# CascaMesa.net
KiCad netlist of a schematic drawn in EAGLE
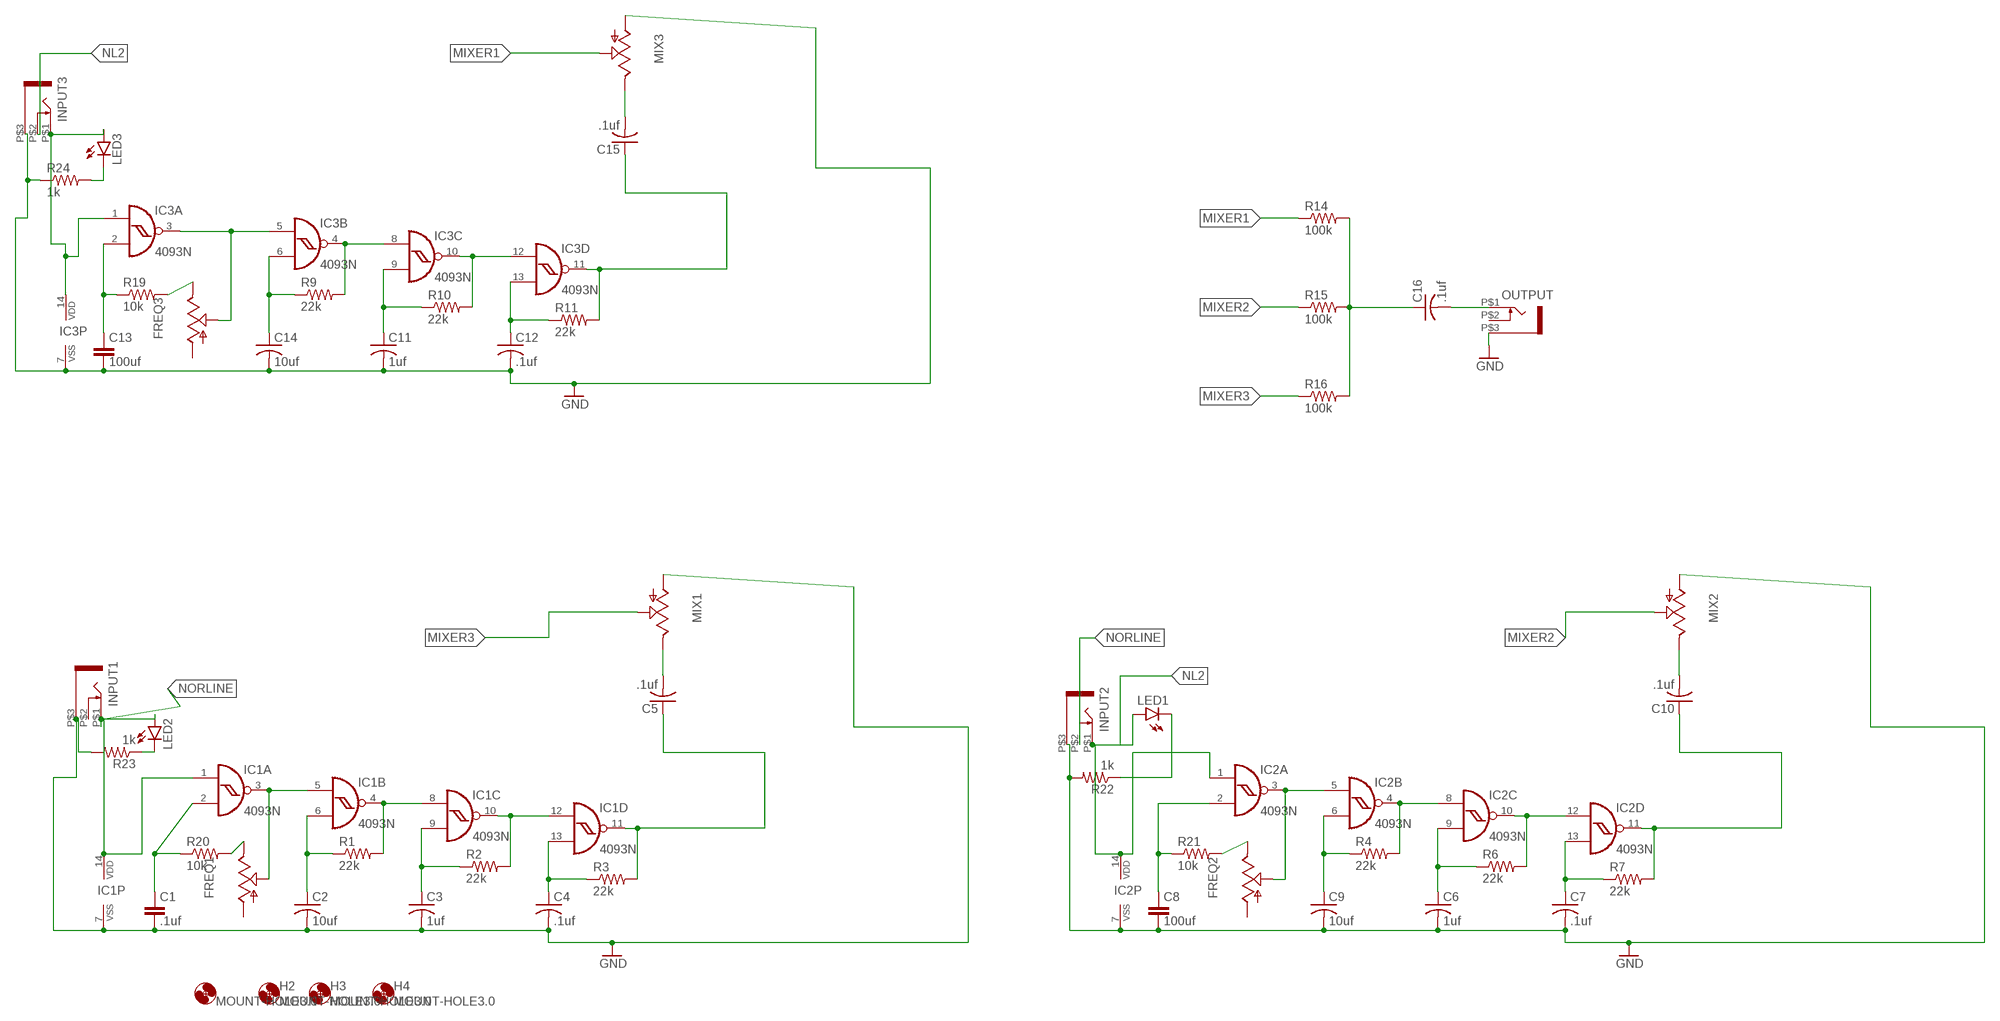
[diagram p0: schematic, sheet 1]

(export (version "E")
  (design (tool "Eeschema 10.0.6"))
  (components
    (comp (ref "C1")
      (value ".1uf")
      (footprint "eagle-import:C050-025X075")
      (libsource (lib "eagle-import") (part "C-EU050-025X075"))
    )
    (comp (ref "C2")
      (value "10uf")
      (footprint "eagle-import:C050-025X075")
      (libsource (lib "eagle-import") (part "C-US050-025X075"))
    )
    (comp (ref "C3")
      (value "1uf")
      (footprint "eagle-import:C050-025X075")
      (libsource (lib "eagle-import") (part "C-US050-025X075"))
    )
    (comp (ref "C4")
      (value ".1uf")
      (footprint "eagle-import:C050-025X075")
      (libsource (lib "eagle-import") (part "C-US050-025X075"))
    )
    (comp (ref "C5")
      (value ".1uf")
      (footprint "eagle-import:C050-025X075")
      (libsource (lib "eagle-import") (part "C-US050-025X075"))
    )
    (comp (ref "C6")
      (value "1uf")
      (footprint "eagle-import:C050-025X075")
      (libsource (lib "eagle-import") (part "C-US050-025X075"))
    )
    (comp (ref "C7")
      (value ".1uf")
      (footprint "eagle-import:C050-025X075")
      (libsource (lib "eagle-import") (part "C-US050-025X075"))
    )
    (comp (ref "C8")
      (value "100uf")
      (footprint "eagle-import:C050-025X075")
      (libsource (lib "eagle-import") (part "C-EU050-025X075"))
    )
    (comp (ref "C9")
      (value "10uf")
      (footprint "eagle-import:C050-025X075")
      (libsource (lib "eagle-import") (part "C-US050-025X075"))
    )
    (comp (ref "C10")
      (value ".1uf")
      (footprint "eagle-import:C050-025X075")
      (libsource (lib "eagle-import") (part "C-US050-025X075"))
    )
    (comp (ref "C11")
      (value "1uf")
      (footprint "eagle-import:C050-025X075")
      (libsource (lib "eagle-import") (part "C-US050-025X075"))
    )
    (comp (ref "C12")
      (value ".1uf")
      (footprint "eagle-import:C050-025X075")
      (libsource (lib "eagle-import") (part "C-US050-025X075"))
    )
    (comp (ref "C13")
      (value "100uf")
      (footprint "eagle-import:C050-025X075")
      (libsource (lib "eagle-import") (part "C-EU050-025X075"))
    )
    (comp (ref "C14")
      (value "10uf")
      (footprint "eagle-import:C050-025X075")
      (libsource (lib "eagle-import") (part "C-US050-025X075"))
    )
    (comp (ref "C15")
      (value ".1uf")
      (footprint "eagle-import:C050-025X075")
      (libsource (lib "eagle-import") (part "C-US050-025X075"))
    )
    (comp (ref "C16")
      (value ".1uf")
      (footprint "eagle-import:C050-025X075")
      (libsource (lib "eagle-import") (part "C-US050-025X075"))
    )
    (comp (ref "FREQ1")
      (value "9MM_SNAP-IN_POT_")
      (footprint "eagle-import:9MM_SNAP-IN_POT")
      (libsource (lib "eagle-import") (part "9MM_SNAP-IN_POT_"))
    )
    (comp (ref "FREQ2")
      (value "9MM_SNAP-IN_POT_")
      (footprint "eagle-import:9MM_SNAP-IN_POT")
      (libsource (lib "eagle-import") (part "9MM_SNAP-IN_POT_"))
    )
    (comp (ref "FREQ3")
      (value "9MM_SNAP-IN_POT_")
      (footprint "eagle-import:9MM_SNAP-IN_POT")
      (libsource (lib "eagle-import") (part "9MM_SNAP-IN_POT_"))
    )
    (comp (ref "H1")
      (value "MOUNT-HOLE3.0")
      (footprint "eagle-import:3,0")
      (libsource (lib "eagle-import") (part "MOUNT-HOLE3.0"))
    )
    (comp (ref "H2")
      (value "MOUNT-HOLE3.0")
      (footprint "eagle-import:3,0")
      (libsource (lib "eagle-import") (part "MOUNT-HOLE3.0"))
    )
    (comp (ref "H3")
      (value "MOUNT-HOLE3.0")
      (footprint "eagle-import:3,0")
      (libsource (lib "eagle-import") (part "MOUNT-HOLE3.0"))
    )
    (comp (ref "H4")
      (value "MOUNT-HOLE3.0")
      (footprint "eagle-import:3,0")
      (libsource (lib "eagle-import") (part "MOUNT-HOLE3.0"))
    )
    (comp (ref "IC1")
      (value "4093N")
      (footprint "eagle-import:DIL14")
      (libsource (lib "eagle-import") (part "4093N"))
    )
    (comp (ref "IC2")
      (value "4093N")
      (footprint "eagle-import:DIL14")
      (libsource (lib "eagle-import") (part "4093N"))
    )
    (comp (ref "IC3")
      (value "4093N")
      (footprint "eagle-import:DIL14")
      (libsource (lib "eagle-import") (part "4093N"))
    )
    (comp (ref "INPUT1")
      (value "WQP-PJ301M-12_JACK")
      (footprint "eagle-import:WQP-PJ301M-12_JACK")
      (libsource (lib "eagle-import") (part "WQP-PJ301M-12_JACK"))
    )
    (comp (ref "INPUT2")
      (value "WQP-PJ301M-12_JACK")
      (footprint "eagle-import:WQP-PJ301M-12_JACK")
      (libsource (lib "eagle-import") (part "WQP-PJ301M-12_JACK"))
    )
    (comp (ref "INPUT3")
      (value "WQP-PJ301M-12_JACK")
      (footprint "eagle-import:WQP-PJ301M-12_JACK")
      (libsource (lib "eagle-import") (part "WQP-PJ301M-12_JACK"))
    )
    (comp (ref "LED1")
      (value "LED3MM")
      (footprint "eagle-import:LED3MM")
      (libsource (lib "eagle-import") (part "LED3MM"))
    )
    (comp (ref "LED2")
      (value "LED3MM")
      (footprint "eagle-import:LED3MM")
      (libsource (lib "eagle-import") (part "LED3MM"))
    )
    (comp (ref "LED3")
      (value "LED3MM")
      (footprint "eagle-import:LED3MM")
      (libsource (lib "eagle-import") (part "LED3MM"))
    )
    (comp (ref "MIX1")
      (value "9MM_SNAP-IN_POT_")
      (footprint "eagle-import:9MM_SNAP-IN_POT")
      (libsource (lib "eagle-import") (part "9MM_SNAP-IN_POT_"))
    )
    (comp (ref "MIX2")
      (value "9MM_SNAP-IN_POT_")
      (footprint "eagle-import:9MM_SNAP-IN_POT")
      (libsource (lib "eagle-import") (part "9MM_SNAP-IN_POT_"))
    )
    (comp (ref "MIX3")
      (value "9MM_SNAP-IN_POT_")
      (footprint "eagle-import:9MM_SNAP-IN_POT")
      (libsource (lib "eagle-import") (part "9MM_SNAP-IN_POT_"))
    )
    (comp (ref "OUTPUT")
      (value "WQP-PJ301M-12_JACK")
      (footprint "eagle-import:WQP-PJ301M-12_JACK")
      (libsource (lib "eagle-import") (part "WQP-PJ301M-12_JACK"))
    )
    (comp (ref "R1")
      (value "22k")
      (footprint "eagle-import:0207_7")
      (libsource (lib "eagle-import") (part "R-US_0207/7"))
    )
    (comp (ref "R2")
      (value "22k")
      (footprint "eagle-import:0207_7")
      (libsource (lib "eagle-import") (part "R-US_0207/7"))
    )
    (comp (ref "R3")
      (value "22k")
      (footprint "eagle-import:0207_7")
      (libsource (lib "eagle-import") (part "R-US_0207/7"))
    )
    (comp (ref "R4")
      (value "22k")
      (footprint "eagle-import:0207_7")
      (libsource (lib "eagle-import") (part "R-US_0207/7"))
    )
    (comp (ref "R6")
      (value "22k")
      (footprint "eagle-import:0207_7")
      (libsource (lib "eagle-import") (part "R-US_0207/7"))
    )
    (comp (ref "R7")
      (value "22k")
      (footprint "eagle-import:0207_7")
      (libsource (lib "eagle-import") (part "R-US_0207/7"))
    )
    (comp (ref "R9")
      (value "22k")
      (footprint "eagle-import:0207_7")
      (libsource (lib "eagle-import") (part "R-US_0207/7"))
    )
    (comp (ref "R10")
      (value "22k")
      (footprint "eagle-import:0207_7")
      (libsource (lib "eagle-import") (part "R-US_0207/7"))
    )
    (comp (ref "R11")
      (value "22k")
      (footprint "eagle-import:0207_7")
      (libsource (lib "eagle-import") (part "R-US_0207/7"))
    )
    (comp (ref "R14")
      (value "100k")
      (footprint "eagle-import:0207_7")
      (libsource (lib "eagle-import") (part "R-US_0207/7"))
    )
    (comp (ref "R15")
      (value "100k")
      (footprint "eagle-import:0207_7")
      (libsource (lib "eagle-import") (part "R-US_0207/7"))
    )
    (comp (ref "R16")
      (value "100k")
      (footprint "eagle-import:0207_7")
      (libsource (lib "eagle-import") (part "R-US_0207/7"))
    )
    (comp (ref "R19")
      (value "10k")
      (footprint "eagle-import:0207_7")
      (libsource (lib "eagle-import") (part "R-US_0207/7"))
    )
    (comp (ref "R20")
      (value "10k")
      (footprint "eagle-import:0207_7")
      (libsource (lib "eagle-import") (part "R-US_0207/7"))
    )
    (comp (ref "R21")
      (value "10k")
      (footprint "eagle-import:0207_7")
      (libsource (lib "eagle-import") (part "R-US_0207/7"))
    )
    (comp (ref "R22")
      (value "1k")
      (footprint "eagle-import:0207_7")
      (libsource (lib "eagle-import") (part "R-US_0207/7"))
    )
    (comp (ref "R23")
      (value "1k")
      (footprint "eagle-import:0207_7")
      (libsource (lib "eagle-import") (part "R-US_0207/7"))
    )
    (comp (ref "R24")
      (value "1k")
      (footprint "eagle-import:0207_7")
      (libsource (lib "eagle-import") (part "R-US_0207/7"))
    )
  )
  (nets
    (net (code "1") (name "GND") (class "Default")
      (node (ref "C1") (pin "2") (pinfunction "2_2") (pintype "passive"))
      (node (ref "C11") (pin "2") (pinfunction "2_2") (pintype "passive"))
      (node (ref "C12") (pin "2") (pinfunction "2_2") (pintype "passive"))
      (node (ref "C13") (pin "2") (pinfunction "2_2") (pintype "passive"))
      (node (ref "C14") (pin "2") (pinfunction "2_2") (pintype "passive"))
      (node (ref "C2") (pin "2") (pinfunction "2_2") (pintype "passive"))
      (node (ref "C3") (pin "2") (pinfunction "2_2") (pintype "passive"))
      (node (ref "C4") (pin "2") (pinfunction "2_2") (pintype "passive"))
      (node (ref "C6") (pin "2") (pinfunction "2_2") (pintype "passive"))
      (node (ref "C7") (pin "2") (pinfunction "2_2") (pintype "passive"))
      (node (ref "C8") (pin "2") (pinfunction "2_2") (pintype "passive"))
      (node (ref "C9") (pin "2") (pinfunction "2_2") (pintype "passive"))
      (node (ref "IC1") (pin "7") (pinfunction "VSS_7") (pintype "power_in"))
      (node (ref "IC2") (pin "7") (pinfunction "VSS_7") (pintype "power_in"))
      (node (ref "IC3") (pin "7") (pinfunction "VSS_7") (pintype "power_in"))
      (node (ref "INPUT1") (pin "P$3") (pinfunction "1_P$3") (pintype "passive"))
      (node (ref "INPUT2") (pin "P$3") (pinfunction "1_P$3") (pintype "passive"))
      (node (ref "INPUT3") (pin "P$3") (pinfunction "1_P$3") (pintype "passive"))
      (node (ref "MIX1") (pin "1") (pinfunction "A_1") (pintype "passive"))
      (node (ref "MIX2") (pin "1") (pinfunction "A_1") (pintype "passive"))
      (node (ref "MIX3") (pin "1") (pinfunction "A_1") (pintype "passive"))
      (node (ref "OUTPUT") (pin "P$3") (pinfunction "1_P$3") (pintype "passive"))
      (node (ref "R22") (pin "2") (pinfunction "2_2") (pintype "passive"))
      (node (ref "R23") (pin "2") (pinfunction "2_2") (pintype "passive"))
      (node (ref "R24") (pin "1") (pinfunction "1_1") (pintype "passive"))
    )
    (net (code "2") (name "MIXER1") (class "Default")
      (node (ref "MIX3") (pin "2") (pinfunction "S_2") (pintype "passive"))
      (node (ref "R14") (pin "1") (pinfunction "1_1") (pintype "passive"))
    )
    (net (code "3") (name "MIXER2") (class "Default")
      (node (ref "MIX2") (pin "2") (pinfunction "S_2") (pintype "passive"))
      (node (ref "R15") (pin "1") (pinfunction "1_1") (pintype "passive"))
    )
    (net (code "4") (name "MIXER3") (class "Default")
      (node (ref "MIX1") (pin "2") (pinfunction "S_2") (pintype "passive"))
      (node (ref "R16") (pin "1") (pinfunction "1_1") (pintype "passive"))
    )
    (net (code "5") (name "NL2") (class "Default")
      (node (ref "IC2") (pin "1") (pinfunction "I0_1") (pintype "input"))
      (node (ref "IC2") (pin "14") (pinfunction "VDD_14") (pintype "power_in"))
      (node (ref "INPUT2") (pin "P$1") (pinfunction "2_P$1") (pintype "passive"))
      (node (ref "INPUT3") (pin "P$2") (pinfunction "3_P$2") (pintype "passive"))
      (node (ref "LED1") (pin "A") (pinfunction "A_A") (pintype "passive"))
    )
    (net (code "6") (name "NORLINE") (class "Default")
      (node (ref "IC1") (pin "1") (pinfunction "I0_1") (pintype "input"))
      (node (ref "IC1") (pin "14") (pinfunction "VDD_14") (pintype "power_in"))
      (node (ref "INPUT1") (pin "P$1") (pinfunction "2_P$1") (pintype "passive"))
      (node (ref "INPUT2") (pin "P$2") (pinfunction "3_P$2") (pintype "passive"))
      (node (ref "LED2") (pin "A") (pinfunction "A_A") (pintype "passive"))
    )
    (net (code "7") (name "Net-(C16-Pad1)") (class "Default")
      (node (ref "C16") (pin "1") (pinfunction "1_1") (pintype "passive"))
      (node (ref "R14") (pin "2") (pinfunction "2_2") (pintype "passive"))
      (node (ref "R15") (pin "2") (pinfunction "2_2") (pintype "passive"))
      (node (ref "R16") (pin "2") (pinfunction "2_2") (pintype "passive"))
    )
    (net (code "8") (name "Net-(FREQ1-E)") (class "Default")
      (node (ref "FREQ1") (pin "3") (pinfunction "E_3") (pintype "passive"))
      (node (ref "R20") (pin "2") (pinfunction "2_2") (pintype "passive"))
    )
    (net (code "9") (name "Net-(FREQ1-S)") (class "Default")
      (node (ref "FREQ1") (pin "2") (pinfunction "S_2") (pintype "passive"))
      (node (ref "IC1") (pin "3") (pinfunction "O_3") (pintype "output"))
      (node (ref "IC1") (pin "5") (pinfunction "I0_5") (pintype "input"))
    )
    (net (code "10") (name "Net-(FREQ2-E)") (class "Default")
      (node (ref "FREQ2") (pin "3") (pinfunction "E_3") (pintype "passive"))
      (node (ref "R21") (pin "2") (pinfunction "2_2") (pintype "passive"))
    )
    (net (code "11") (name "Net-(FREQ2-S)") (class "Default")
      (node (ref "FREQ2") (pin "2") (pinfunction "S_2") (pintype "passive"))
      (node (ref "IC2") (pin "3") (pinfunction "O_3") (pintype "output"))
      (node (ref "IC2") (pin "5") (pinfunction "I0_5") (pintype "input"))
    )
    (net (code "12") (name "Net-(FREQ3-E)") (class "Default")
      (node (ref "FREQ3") (pin "3") (pinfunction "E_3") (pintype "passive"))
      (node (ref "R19") (pin "2") (pinfunction "2_2") (pintype "passive"))
    )
    (net (code "13") (name "Net-(FREQ3-S)") (class "Default")
      (node (ref "FREQ3") (pin "2") (pinfunction "S_2") (pintype "passive"))
      (node (ref "IC3") (pin "3") (pinfunction "O_3") (pintype "output"))
      (node (ref "IC3") (pin "5") (pinfunction "I0_5") (pintype "input"))
    )
    (net (code "14") (name "Net-(IC1A-I1)") (class "Default")
      (node (ref "C1") (pin "1") (pinfunction "1_1") (pintype "passive"))
      (node (ref "IC1") (pin "2") (pinfunction "I1_2") (pintype "input"))
      (node (ref "R20") (pin "1") (pinfunction "1_1") (pintype "passive"))
    )
    (net (code "15") (name "Net-(IC1B-I1)") (class "Default")
      (node (ref "C2") (pin "1") (pinfunction "1_1") (pintype "passive"))
      (node (ref "IC1") (pin "6") (pinfunction "I1_6") (pintype "input"))
      (node (ref "R1") (pin "1") (pinfunction "1_1") (pintype "passive"))
    )
    (net (code "16") (name "Net-(IC1B-O)") (class "Default")
      (node (ref "IC1") (pin "4") (pinfunction "O_4") (pintype "output"))
      (node (ref "IC1") (pin "8") (pinfunction "I0_8") (pintype "input"))
      (node (ref "R1") (pin "2") (pinfunction "2_2") (pintype "passive"))
    )
    (net (code "17") (name "Net-(IC1C-I1)") (class "Default")
      (node (ref "C3") (pin "1") (pinfunction "1_1") (pintype "passive"))
      (node (ref "IC1") (pin "9") (pinfunction "I1_9") (pintype "input"))
      (node (ref "R2") (pin "1") (pinfunction "1_1") (pintype "passive"))
    )
    (net (code "18") (name "Net-(IC1C-O)") (class "Default")
      (node (ref "IC1") (pin "10") (pinfunction "O_10") (pintype "output"))
      (node (ref "IC1") (pin "12") (pinfunction "I0_12") (pintype "input"))
      (node (ref "R2") (pin "2") (pinfunction "2_2") (pintype "passive"))
    )
    (net (code "19") (name "Net-(IC1D-I1)") (class "Default")
      (node (ref "C4") (pin "1") (pinfunction "1_1") (pintype "passive"))
      (node (ref "IC1") (pin "13") (pinfunction "I1_13") (pintype "input"))
      (node (ref "R3") (pin "1") (pinfunction "1_1") (pintype "passive"))
    )
    (net (code "20") (name "Net-(IC1D-O)") (class "Default")
      (node (ref "C5") (pin "1") (pinfunction "1_1") (pintype "passive"))
      (node (ref "IC1") (pin "11") (pinfunction "O_11") (pintype "output"))
      (node (ref "R3") (pin "2") (pinfunction "2_2") (pintype "passive"))
    )
    (net (code "21") (name "Net-(IC2A-I1)") (class "Default")
      (node (ref "C8") (pin "1") (pinfunction "1_1") (pintype "passive"))
      (node (ref "IC2") (pin "2") (pinfunction "I1_2") (pintype "input"))
      (node (ref "R21") (pin "1") (pinfunction "1_1") (pintype "passive"))
    )
    (net (code "22") (name "Net-(IC2B-I1)") (class "Default")
      (node (ref "C9") (pin "1") (pinfunction "1_1") (pintype "passive"))
      (node (ref "IC2") (pin "6") (pinfunction "I1_6") (pintype "input"))
      (node (ref "R4") (pin "1") (pinfunction "1_1") (pintype "passive"))
    )
    (net (code "23") (name "Net-(IC2B-O)") (class "Default")
      (node (ref "IC2") (pin "4") (pinfunction "O_4") (pintype "output"))
      (node (ref "IC2") (pin "8") (pinfunction "I0_8") (pintype "input"))
      (node (ref "R4") (pin "2") (pinfunction "2_2") (pintype "passive"))
    )
    (net (code "24") (name "Net-(IC2C-I1)") (class "Default")
      (node (ref "C6") (pin "1") (pinfunction "1_1") (pintype "passive"))
      (node (ref "IC2") (pin "9") (pinfunction "I1_9") (pintype "input"))
      (node (ref "R6") (pin "1") (pinfunction "1_1") (pintype "passive"))
    )
    (net (code "25") (name "Net-(IC2C-O)") (class "Default")
      (node (ref "IC2") (pin "10") (pinfunction "O_10") (pintype "output"))
      (node (ref "IC2") (pin "12") (pinfunction "I0_12") (pintype "input"))
      (node (ref "R6") (pin "2") (pinfunction "2_2") (pintype "passive"))
    )
    (net (code "26") (name "Net-(IC2D-I1)") (class "Default")
      (node (ref "C7") (pin "1") (pinfunction "1_1") (pintype "passive"))
      (node (ref "IC2") (pin "13") (pinfunction "I1_13") (pintype "input"))
      (node (ref "R7") (pin "1") (pinfunction "1_1") (pintype "passive"))
    )
    (net (code "27") (name "Net-(IC2D-O)") (class "Default")
      (node (ref "C10") (pin "1") (pinfunction "1_1") (pintype "passive"))
      (node (ref "IC2") (pin "11") (pinfunction "O_11") (pintype "output"))
      (node (ref "R7") (pin "2") (pinfunction "2_2") (pintype "passive"))
    )
    (net (code "28") (name "Net-(IC3A-I0)") (class "Default")
      (node (ref "IC3") (pin "1") (pinfunction "I0_1") (pintype "input"))
      (node (ref "IC3") (pin "14") (pinfunction "VDD_14") (pintype "power_in"))
      (node (ref "INPUT3") (pin "P$1") (pinfunction "2_P$1") (pintype "passive"))
      (node (ref "LED3") (pin "A") (pinfunction "A_A") (pintype "passive"))
    )
    (net (code "29") (name "Net-(IC3A-I1)") (class "Default")
      (node (ref "C13") (pin "1") (pinfunction "1_1") (pintype "passive"))
      (node (ref "IC3") (pin "2") (pinfunction "I1_2") (pintype "input"))
      (node (ref "R19") (pin "1") (pinfunction "1_1") (pintype "passive"))
    )
    (net (code "30") (name "Net-(IC3B-I1)") (class "Default")
      (node (ref "C14") (pin "1") (pinfunction "1_1") (pintype "passive"))
      (node (ref "IC3") (pin "6") (pinfunction "I1_6") (pintype "input"))
      (node (ref "R9") (pin "1") (pinfunction "1_1") (pintype "passive"))
    )
    (net (code "31") (name "Net-(IC3B-O)") (class "Default")
      (node (ref "IC3") (pin "4") (pinfunction "O_4") (pintype "output"))
      (node (ref "IC3") (pin "8") (pinfunction "I0_8") (pintype "input"))
      (node (ref "R9") (pin "2") (pinfunction "2_2") (pintype "passive"))
    )
    (net (code "32") (name "Net-(IC3C-I1)") (class "Default")
      (node (ref "C11") (pin "1") (pinfunction "1_1") (pintype "passive"))
      (node (ref "IC3") (pin "9") (pinfunction "I1_9") (pintype "input"))
      (node (ref "R10") (pin "1") (pinfunction "1_1") (pintype "passive"))
    )
    (net (code "33") (name "Net-(IC3C-O)") (class "Default")
      (node (ref "IC3") (pin "10") (pinfunction "O_10") (pintype "output"))
      (node (ref "IC3") (pin "12") (pinfunction "I0_12") (pintype "input"))
      (node (ref "R10") (pin "2") (pinfunction "2_2") (pintype "passive"))
    )
    (net (code "34") (name "Net-(IC3D-I1)") (class "Default")
      (node (ref "C12") (pin "1") (pinfunction "1_1") (pintype "passive"))
      (node (ref "IC3") (pin "13") (pinfunction "I1_13") (pintype "input"))
      (node (ref "R11") (pin "1") (pinfunction "1_1") (pintype "passive"))
    )
    (net (code "35") (name "Net-(IC3D-O)") (class "Default")
      (node (ref "C15") (pin "1") (pinfunction "1_1") (pintype "passive"))
      (node (ref "IC3") (pin "11") (pinfunction "O_11") (pintype "output"))
      (node (ref "R11") (pin "2") (pinfunction "2_2") (pintype "passive"))
    )
    (net (code "36") (name "Net-(LED1-C)") (class "Default")
      (node (ref "LED1") (pin "K") (pinfunction "C_K") (pintype "passive"))
      (node (ref "R22") (pin "1") (pinfunction "1_1") (pintype "passive"))
    )
    (net (code "37") (name "Net-(LED2-C)") (class "Default")
      (node (ref "LED2") (pin "K") (pinfunction "C_K") (pintype "passive"))
      (node (ref "R23") (pin "1") (pinfunction "1_1") (pintype "passive"))
    )
    (net (code "38") (name "Net-(LED3-C)") (class "Default")
      (node (ref "LED3") (pin "K") (pinfunction "C_K") (pintype "passive"))
      (node (ref "R24") (pin "2") (pinfunction "2_2") (pintype "passive"))
    )
    (net (code "39") (name "Net-(MIX1-E)") (class "Default")
      (node (ref "C5") (pin "2") (pinfunction "2_2") (pintype "passive"))
      (node (ref "MIX1") (pin "3") (pinfunction "E_3") (pintype "passive"))
    )
    (net (code "40") (name "Net-(MIX2-E)") (class "Default")
      (node (ref "C10") (pin "2") (pinfunction "2_2") (pintype "passive"))
      (node (ref "MIX2") (pin "3") (pinfunction "E_3") (pintype "passive"))
    )
    (net (code "41") (name "Net-(MIX3-E)") (class "Default")
      (node (ref "C15") (pin "2") (pinfunction "2_2") (pintype "passive"))
      (node (ref "MIX3") (pin "3") (pinfunction "E_3") (pintype "passive"))
    )
    (net (code "42") (name "Net-(OUTPUT-2)") (class "Default")
      (node (ref "C16") (pin "2") (pinfunction "2_2") (pintype "passive"))
      (node (ref "OUTPUT") (pin "P$1") (pinfunction "2_P$1") (pintype "passive"))
    )
    (net (code "43") (name "unconnected-(FREQ1-A-Pad1)") (class "Default")
      (node (ref "FREQ1") (pin "1") (pinfunction "A_1") (pintype "passive"))
    )
    (net (code "44") (name "unconnected-(FREQ2-A-Pad1)") (class "Default")
      (node (ref "FREQ2") (pin "1") (pinfunction "A_1") (pintype "passive"))
    )
    (net (code "45") (name "unconnected-(FREQ3-A-Pad1)") (class "Default")
      (node (ref "FREQ3") (pin "1") (pinfunction "A_1") (pintype "passive"))
    )
    (net (code "46") (name "unconnected-(INPUT1-3-PadP$2)") (class "Default")
      (node (ref "INPUT1") (pin "P$2") (pinfunction "3_P$2") (pintype "passive"))
    )
    (net (code "47") (name "unconnected-(OUTPUT-3-PadP$2)") (class "Default")
      (node (ref "OUTPUT") (pin "P$2") (pinfunction "3_P$2") (pintype "passive"))
    )
  )
)
